# middleManBoard.net
KiCad netlist of a schematic drawn in Altium Designer
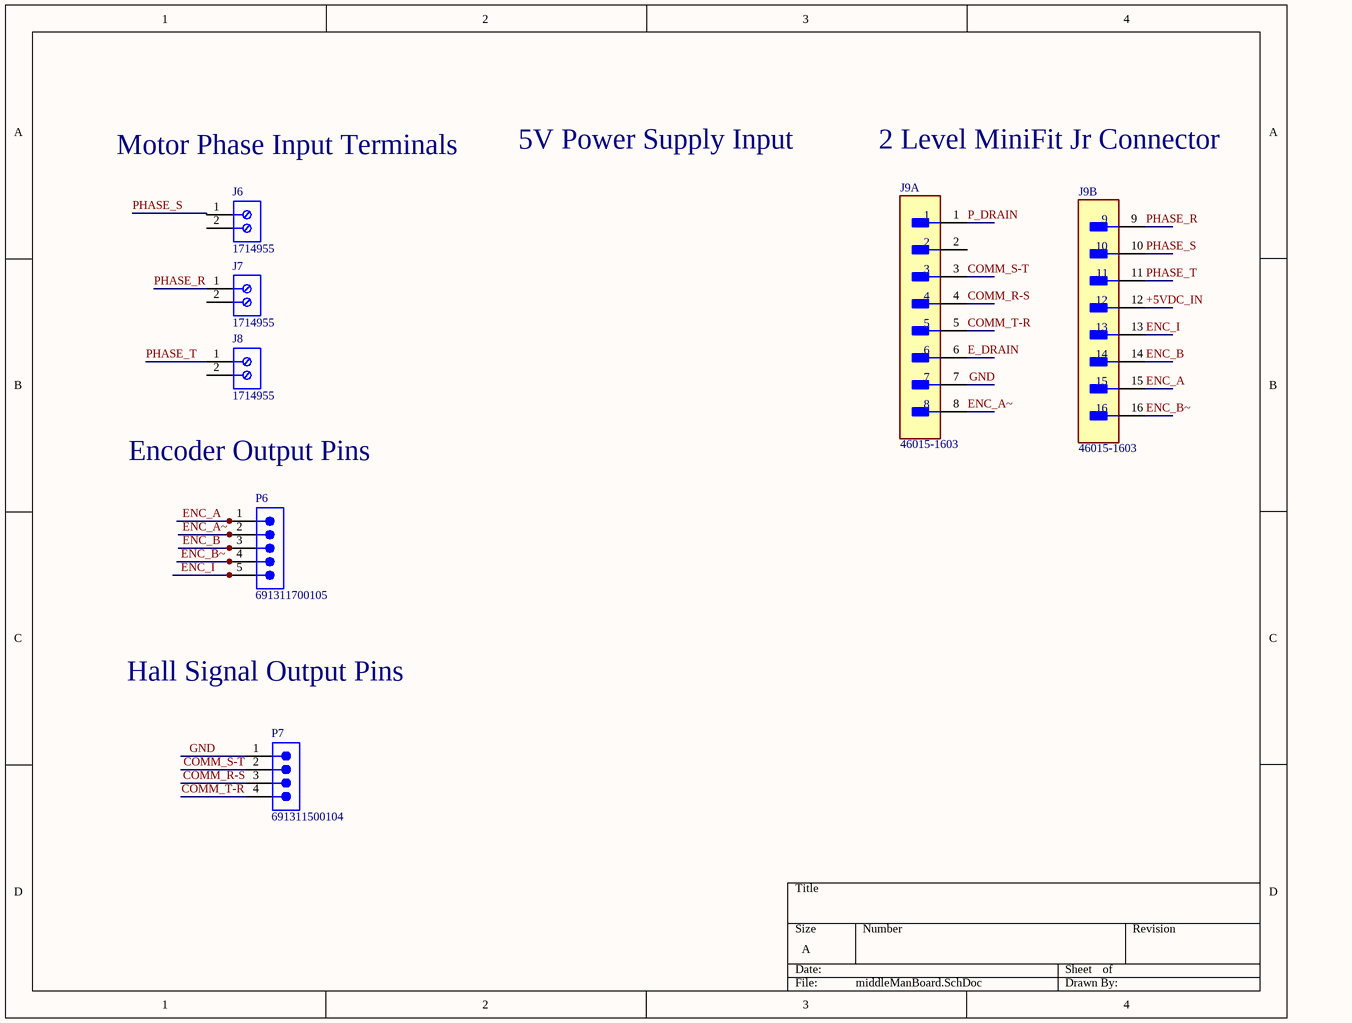
[diagram p0: middleManBoard.SchDoc]

(export (version "E")
  (design (tool "Eeschema 10.0.6"))
  (components
    (comp (ref "J6")
      (value "1714955")
      (footprint "PHOE-1714955_V")
      (description "PC Terminal Block, Pitch 6.35 mm, 1 x 2 Position, Height 21.5 mm, Tail Lenght 5.1 mm, RoHS, Bulk")
      (fields (field (name "MANUFACTURER") "Phoenix Contact"))
      (libsource (lib "Altium Content Vault") (part "CN-1P-F-TB2"))
    )
    (comp (ref "J7")
      (value "1714955")
      (footprint "PHOE-1714955_V")
      (description "PC Terminal Block, Pitch 6.35 mm, 1 x 2 Position, Height 21.5 mm, Tail Lenght 5.1 mm, RoHS, Bulk")
      (fields (field (name "MANUFACTURER") "Phoenix Contact"))
      (libsource (lib "Altium Content Vault") (part "CN-1P-F-TB2"))
    )
    (comp (ref "J8")
      (value "1714955")
      (footprint "PHOE-1714955_V")
      (description "PC Terminal Block, Pitch 6.35 mm, 1 x 2 Position, Height 21.5 mm, Tail Lenght 5.1 mm, RoHS, Bulk")
      (fields (field (name "MANUFACTURER") "Phoenix Contact"))
      (libsource (lib "Altium Content Vault") (part "CN-1P-F-TB2"))
    )
    (comp (ref "J9")
      (value "46015-1603")
      (footprint "FP-46015-1603-MFG")
      (description "CONN HEADER VERT 16POS 4.2MM")
      (libsource (lib "molexMiniFitJr_component") (part "CMP-04776-001032-1"))
    )
    (comp (ref "P6")
      (value "691311700105")
      (footprint "691311700105")
      (fields (field (name "VOLTAGE") "300V"))
      (libsource (lib "Altium Content Vault") (part "TBL - 1R - 05P - Male"))
    )
    (comp (ref "P7")
      (value "691311500104")
      (footprint "691311500104")
      (fields (field (name "VOLTAGE") "300V"))
      (libsource (lib "Altium Content Vault") (part "TBL - 1R - 04P - Male"))
    )
  )
  (nets
    (net (code "1") (name "/+5VDC_IN") (class "Default")
      (node (ref "J9") (pin "12") (pinfunction "12_12") (pintype "passive"))
    )
    (net (code "2") (name "/COMM_R-S") (class "Default")
      (node (ref "J9") (pin "4") (pinfunction "4_4") (pintype "passive"))
      (node (ref "P7") (pin "3") (pinfunction "3_3") (pintype "passive"))
    )
    (net (code "3") (name "/COMM_S-T") (class "Default")
      (node (ref "J9") (pin "3") (pinfunction "3_3") (pintype "passive"))
      (node (ref "P7") (pin "2") (pinfunction "2_2") (pintype "passive"))
    )
    (net (code "4") (name "/COMM_T-R") (class "Default")
      (node (ref "J9") (pin "5") (pinfunction "5_5") (pintype "passive"))
      (node (ref "P7") (pin "4") (pinfunction "4_4") (pintype "passive"))
    )
    (net (code "5") (name "/ENC_A") (class "Default")
      (node (ref "J9") (pin "15") (pinfunction "15_15") (pintype "passive"))
      (node (ref "P6") (pin "1") (pinfunction "1_1") (pintype "passive"))
    )
    (net (code "6") (name "/ENC_A~") (class "Default")
      (node (ref "J9") (pin "8") (pinfunction "8_8") (pintype "passive"))
      (node (ref "P6") (pin "2") (pinfunction "2_2") (pintype "passive"))
    )
    (net (code "7") (name "/ENC_B") (class "Default")
      (node (ref "J9") (pin "14") (pinfunction "14_14") (pintype "passive"))
      (node (ref "P6") (pin "3") (pinfunction "3_3") (pintype "passive"))
    )
    (net (code "8") (name "/ENC_B~") (class "Default")
      (node (ref "J9") (pin "16") (pinfunction "16_16") (pintype "passive"))
      (node (ref "P6") (pin "4") (pinfunction "4_4") (pintype "passive"))
    )
    (net (code "9") (name "/ENC_I") (class "Default")
      (node (ref "J9") (pin "13") (pinfunction "13_13") (pintype "passive"))
      (node (ref "P6") (pin "5") (pinfunction "5_5") (pintype "passive"))
    )
    (net (code "10") (name "/E_DRAIN") (class "Default")
      (node (ref "J9") (pin "6") (pinfunction "6_6") (pintype "passive"))
    )
    (net (code "11") (name "/GND") (class "Default")
      (node (ref "J9") (pin "7") (pinfunction "7_7") (pintype "passive"))
      (node (ref "P7") (pin "1") (pinfunction "1_1") (pintype "passive"))
    )
    (net (code "12") (name "/PHASE_R") (class "Default")
      (node (ref "J7") (pin "1") (pinfunction "1_1") (pintype "passive"))
      (node (ref "J9") (pin "9") (pinfunction "9_9") (pintype "passive"))
    )
    (net (code "13") (name "/PHASE_S") (class "Default")
      (node (ref "J6") (pin "1") (pinfunction "1_1") (pintype "passive"))
      (node (ref "J9") (pin "10") (pinfunction "10_10") (pintype "passive"))
    )
    (net (code "14") (name "/PHASE_T") (class "Default")
      (node (ref "J8") (pin "1") (pinfunction "1_1") (pintype "passive"))
      (node (ref "J9") (pin "11") (pinfunction "11_11") (pintype "passive"))
    )
    (net (code "15") (name "/P_DRAIN") (class "Default")
      (node (ref "J9") (pin "1") (pinfunction "1_1") (pintype "passive"))
    )
    (net (code "16") (name "unconnected-(J6-Pad2)") (class "Default")
      (node (ref "J6") (pin "2") (pinfunction "2_2") (pintype "passive"))
    )
    (net (code "17") (name "unconnected-(J7-Pad2)") (class "Default")
      (node (ref "J7") (pin "2") (pinfunction "2_2") (pintype "passive"))
    )
    (net (code "18") (name "unconnected-(J8-Pad2)") (class "Default")
      (node (ref "J8") (pin "2") (pinfunction "2_2") (pintype "passive"))
    )
    (net (code "19") (name "unconnected-(J9-Pad2)") (class "Default")
      (node (ref "J9") (pin "2") (pinfunction "2_2") (pintype "passive"))
    )
  )
)
